# pwr_supply_controller.net
KiCad netlist of a schematic drawn in EAGLE
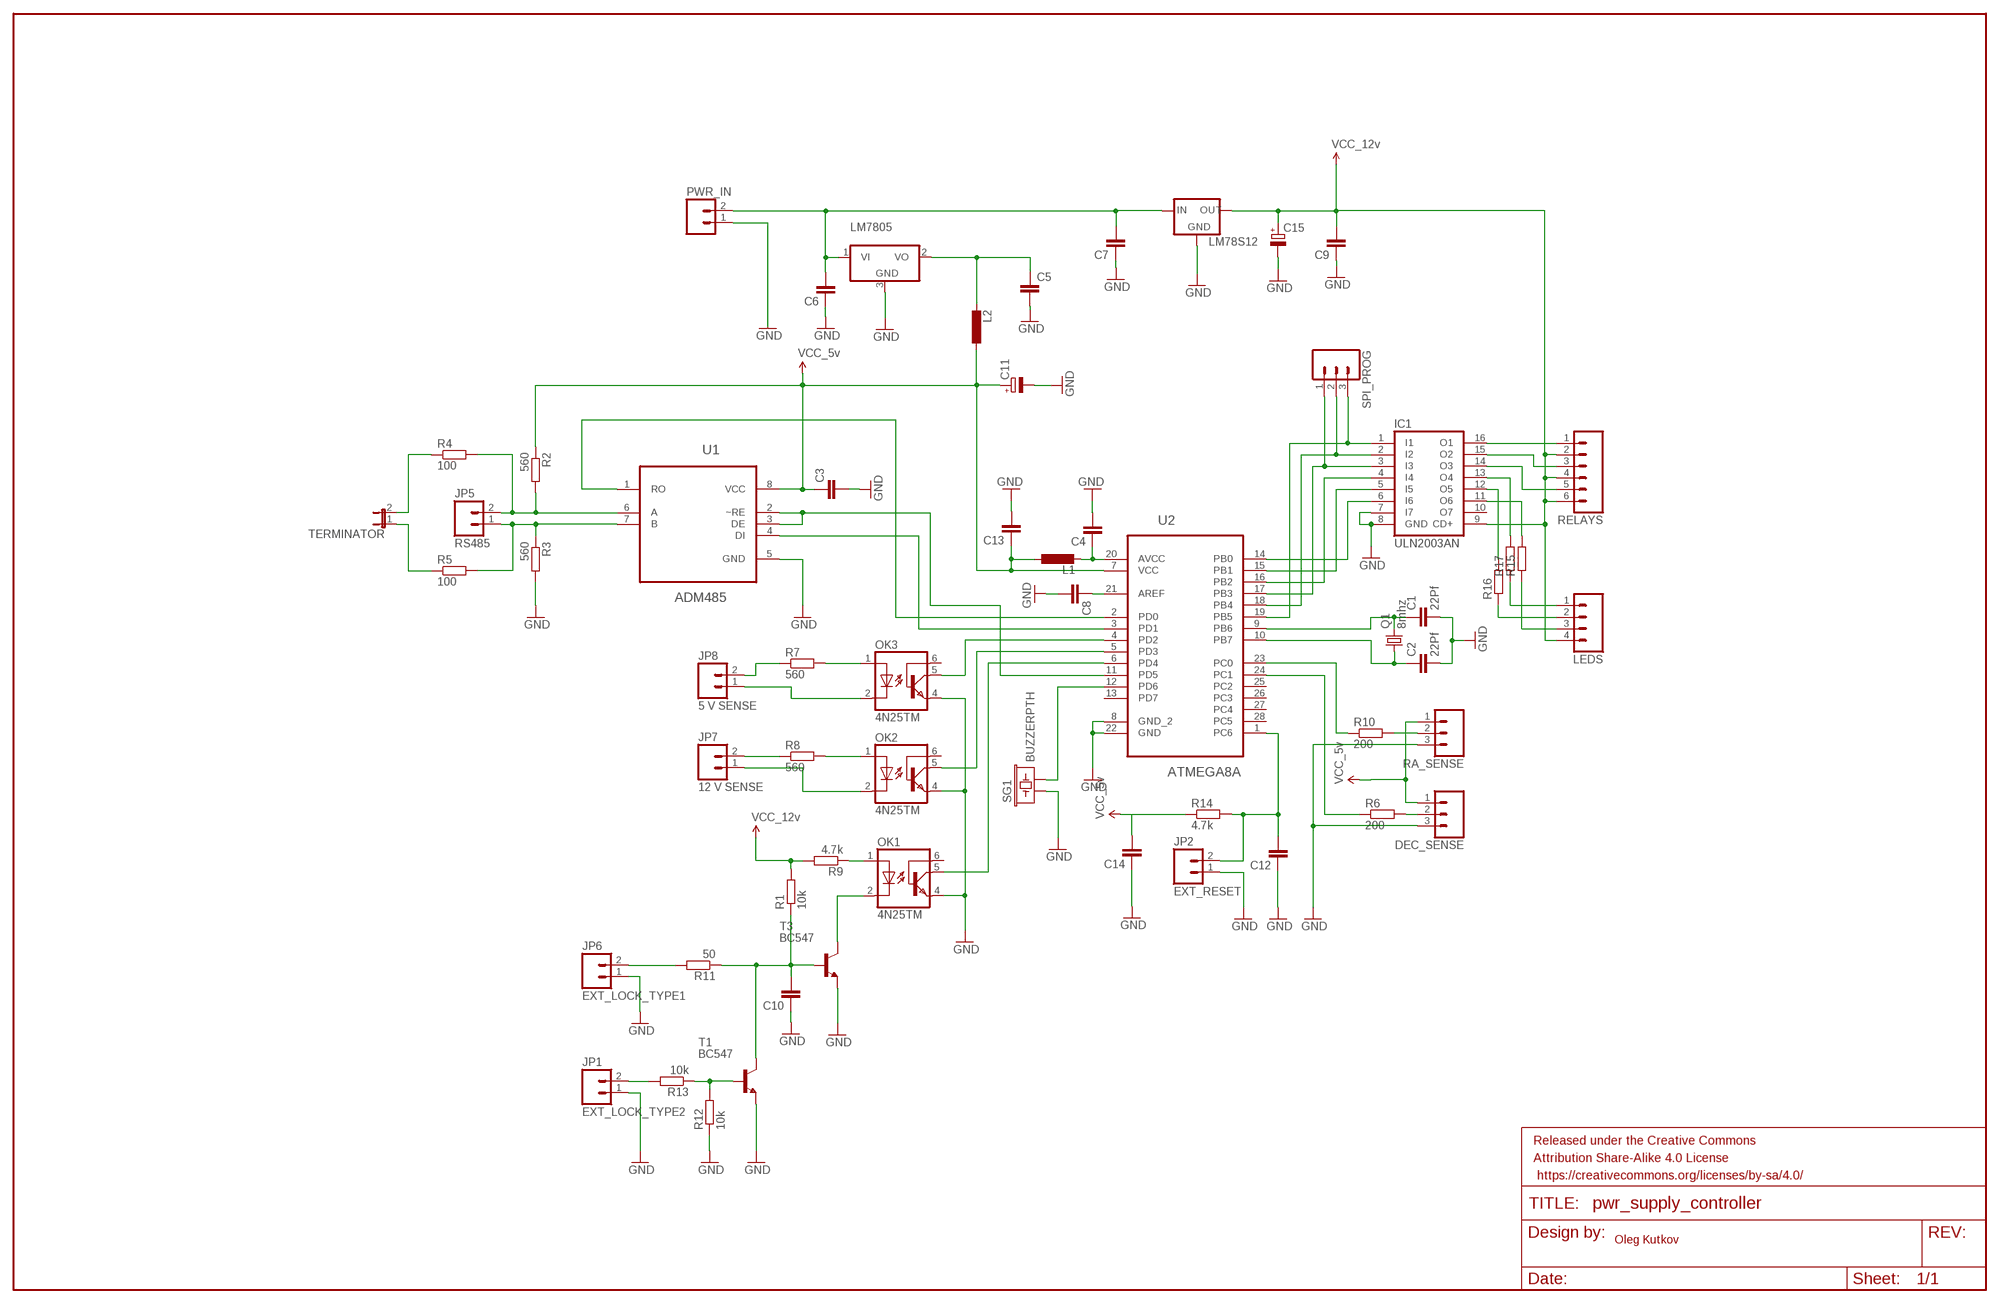
[diagram p0: schematic, sheet 1]

(export (version "E")
  (design (tool "Eeschema 10.0.6"))
  (components
    (comp (ref "C1")
      (value "22Pf")
      (footprint "eagle-import:C0603K")
      (libsource (lib "eagle-import") (part "C-EUC0603K"))
    )
    (comp (ref "C2")
      (value "22Pf")
      (footprint "eagle-import:C0603K")
      (libsource (lib "eagle-import") (part "C-EUC0603K"))
    )
    (comp (ref "C3")
      (value "C-EUC0603K")
      (footprint "eagle-import:C0603K")
      (libsource (lib "eagle-import") (part "C-EUC0603K"))
    )
    (comp (ref "C4")
      (value "C-EUC0603K")
      (footprint "eagle-import:C0603K")
      (libsource (lib "eagle-import") (part "C-EUC0603K"))
    )
    (comp (ref "C5")
      (value "C-EUC0603K")
      (footprint "eagle-import:C0603K")
      (libsource (lib "eagle-import") (part "C-EUC0603K"))
    )
    (comp (ref "C6")
      (value "C-EUC0805")
      (footprint "eagle-import:C0805")
      (libsource (lib "eagle-import") (part "C-EUC0805"))
    )
    (comp (ref "C7")
      (value "C-EUC0805")
      (footprint "eagle-import:C0805")
      (libsource (lib "eagle-import") (part "C-EUC0805"))
    )
    (comp (ref "C8")
      (value "C-EUC0603K")
      (footprint "eagle-import:C0603K")
      (libsource (lib "eagle-import") (part "C-EUC0603K"))
    )
    (comp (ref "C9")
      (value "C-EUC0805")
      (footprint "eagle-import:C0805")
      (libsource (lib "eagle-import") (part "C-EUC0805"))
    )
    (comp (ref "C10")
      (value "C-EUC0603K")
      (footprint "eagle-import:C0603K")
      (libsource (lib "eagle-import") (part "C-EUC0603K"))
    )
    (comp (ref "C11")
      (value "CPOL-EUE2-5")
      (footprint "eagle-import:E2-5")
      (libsource (lib "eagle-import") (part "CPOL-EUE2-5"))
    )
    (comp (ref "C12")
      (value "C-EUC0603K")
      (footprint "eagle-import:C0603K")
      (libsource (lib "eagle-import") (part "C-EUC0603K"))
    )
    (comp (ref "C13")
      (value "C-EUC0603K")
      (footprint "eagle-import:C0603K")
      (libsource (lib "eagle-import") (part "C-EUC0603K"))
    )
    (comp (ref "C14")
      (value "C-EUC0603K")
      (footprint "eagle-import:C0603K")
      (libsource (lib "eagle-import") (part "C-EUC0603K"))
    )
    (comp (ref "C15")
      (value "CPOL-EUE3.5-8")
      (footprint "eagle-import:E3,5-8")
      (libsource (lib "eagle-import") (part "CPOL-EUE3.5-8"))
    )
    (comp (ref "DEC_SENSE")
      (value "M03PTH")
      (footprint "eagle-import:1X03")
      (libsource (lib "eagle-import") (part "M03PTH"))
    )
    (comp (ref "FRAME1")
      (value "FRAME-LEDGER")
      (footprint "eagle-import:CREATIVE_COMMONS")
      (libsource (lib "eagle-import") (part "FRAME-LEDGER"))
    )
    (comp (ref "IC1")
      (value "ULN2003AN")
      (footprint "eagle-import:DIL16")
      (libsource (lib "eagle-import") (part "ULN2003AN"))
    )
    (comp (ref "JP1")
      (value "EXT_LOCK_TYPE2")
      (footprint "eagle-import:JST-2-PTH-VERT")
      (libsource (lib "eagle-import") (part "M02JST-PTH-VERT"))
    )
    (comp (ref "JP2")
      (value "EXT_RESET")
      (footprint "eagle-import:1X02")
      (libsource (lib "eagle-import") (part "M02PTH"))
    )
    (comp (ref "JP5")
      (value "RS485")
      (footprint "eagle-import:JST-2-PTH-VERT")
      (libsource (lib "eagle-import") (part "M02JST-PTH-VERT"))
    )
    (comp (ref "JP6")
      (value "EXT_LOCK_TYPE1")
      (footprint "eagle-import:JST-2-PTH-VERT")
      (libsource (lib "eagle-import") (part "M02JST-PTH-VERT"))
    )
    (comp (ref "JP7")
      (value "12 V SENSE")
      (footprint "eagle-import:JST-2-PTH-VERT")
      (libsource (lib "eagle-import") (part "M02JST-PTH-VERT"))
    )
    (comp (ref "JP8")
      (value "5 V SENSE")
      (footprint "eagle-import:JST-2-PTH-VERT")
      (libsource (lib "eagle-import") (part "M02JST-PTH-VERT"))
    )
    (comp (ref "L1")
      (value "L-EU0204/7")
      (footprint "eagle-import:0204_7")
      (libsource (lib "eagle-import") (part "L-EU0204/7"))
    )
    (comp (ref "L2")
      (value "L-EU0204/7")
      (footprint "eagle-import:0204_7")
      (libsource (lib "eagle-import") (part "L-EU0204/7"))
    )
    (comp (ref "LEDS")
      (value "M04PTH")
      (footprint "eagle-import:1X04")
      (libsource (lib "eagle-import") (part "M04PTH"))
    )
    (comp (ref "LM78S12")
      (value "V_REG_78XX-TO-220")
      (footprint "eagle-import:TO-220-ALT")
      (libsource (lib "eagle-import") (part "V_REG_78XX-TO-220"))
    )
    (comp (ref "LM7805")
      (value "7808DT")
      (footprint "eagle-import:TO252")
      (libsource (lib "eagle-import") (part "78DT08"))
    )
    (comp (ref "OK1")
      (value "4N25TM")
      (footprint "eagle-import:DIL6-04")
      (libsource (lib "eagle-import") (part "4N?MT25"))
    )
    (comp (ref "OK2")
      (value "4N25TM")
      (footprint "eagle-import:DIL6-04")
      (libsource (lib "eagle-import") (part "4N?MT25"))
    )
    (comp (ref "OK3")
      (value "4N25TM")
      (footprint "eagle-import:DIL6-04")
      (libsource (lib "eagle-import") (part "4N?MT25"))
    )
    (comp (ref "PWR_IN")
      (value "M02JST-PTH-VERT")
      (footprint "eagle-import:JST-2-PTH-VERT")
      (libsource (lib "eagle-import") (part "M02JST-PTH-VERT"))
    )
    (comp (ref "Q1")
      (value "8mhz")
      (footprint "eagle-import:HC49_S")
      (libsource (lib "eagle-import") (part "CRYSTALHC49S"))
    )
    (comp (ref "R1")
      (value "10k")
      (footprint "eagle-import:0204_7")
      (libsource (lib "eagle-import") (part "resistor_R-EU_0204/7"))
    )
    (comp (ref "R2")
      (value "560")
      (footprint "eagle-import:M0805")
      (libsource (lib "eagle-import") (part "resistor_R-EU_M0805"))
    )
    (comp (ref "R3")
      (value "560")
      (footprint "eagle-import:M0805")
      (libsource (lib "eagle-import") (part "resistor_R-EU_M0805"))
    )
    (comp (ref "R4")
      (value "100")
      (footprint "eagle-import:R0805")
      (libsource (lib "eagle-import") (part "resistor_R-EU_R0805"))
    )
    (comp (ref "R5")
      (value "100")
      (footprint "eagle-import:M0805")
      (libsource (lib "eagle-import") (part "resistor_R-EU_M0805"))
    )
    (comp (ref "R6")
      (value "200")
      (footprint "eagle-import:M0805")
      (libsource (lib "eagle-import") (part "resistor_R-EU_M0805"))
    )
    (comp (ref "R7")
      (value "560")
      (footprint "eagle-import:0204_7")
      (libsource (lib "eagle-import") (part "resistor_R-EU_0204/7"))
    )
    (comp (ref "R8")
      (value "560")
      (footprint "eagle-import:0204_7")
      (libsource (lib "eagle-import") (part "resistor_R-EU_0204/7"))
    )
    (comp (ref "R9")
      (value "4.7k")
      (footprint "eagle-import:0204_7")
      (libsource (lib "eagle-import") (part "resistor_R-EU_0204/7"))
    )
    (comp (ref "R10")
      (value "200")
      (footprint "eagle-import:M0805")
      (libsource (lib "eagle-import") (part "resistor_R-EU_M0805"))
    )
    (comp (ref "R11")
      (value "50")
      (footprint "eagle-import:0204_7")
      (libsource (lib "eagle-import") (part "resistor_R-EU_0204/7"))
    )
    (comp (ref "R12")
      (value "10k")
      (footprint "eagle-import:0204_7")
      (libsource (lib "eagle-import") (part "resistor_R-EU_0204/7"))
    )
    (comp (ref "R13")
      (value "10k")
      (footprint "eagle-import:0204_7")
      (libsource (lib "eagle-import") (part "resistor_R-EU_0204/7"))
    )
    (comp (ref "R14")
      (value "4.7k")
      (footprint "eagle-import:M0805")
      (libsource (lib "eagle-import") (part "resistor_R-EU_M0805"))
    )
    (comp (ref "R15")
      (value "R-EU_M0805")
      (footprint "eagle-import:M0805")
      (libsource (lib "eagle-import") (part "R-EU_M0805"))
    )
    (comp (ref "R16")
      (value "R-EU_M0805")
      (footprint "eagle-import:M0805")
      (libsource (lib "eagle-import") (part "R-EU_M0805"))
    )
    (comp (ref "R17")
      (value "R-EU_M0805")
      (footprint "eagle-import:M0805")
      (libsource (lib "eagle-import") (part "R-EU_M0805"))
    )
    (comp (ref "RA_SENSE")
      (value "M03PTH")
      (footprint "eagle-import:1X03")
      (libsource (lib "eagle-import") (part "M03PTH"))
    )
    (comp (ref "RELAYS")
      (value "M06POLAR")
      (footprint "eagle-import:MOLEX-1X6")
      (libsource (lib "eagle-import") (part "M06POLAR"))
    )
    (comp (ref "SG1")
      (value "BUZZERPTH")
      (footprint "eagle-import:BUZZER-12MM")
      (libsource (lib "eagle-import") (part "BUZZERPTH"))
    )
    (comp (ref "SPI_PROG")
      (value "M03PTH")
      (footprint "eagle-import:1X03")
      (libsource (lib "eagle-import") (part "M03PTH"))
    )
    (comp (ref "T1")
      (value "BC547")
      (footprint "eagle-import:TO92")
      (libsource (lib "eagle-import") (part "BC547"))
    )
    (comp (ref "T3")
      (value "BC547")
      (footprint "eagle-import:TO92")
      (libsource (lib "eagle-import") (part "BC547"))
    )
    (comp (ref "TERMINATOR")
      (value "JUMPER-2PTH_LOCK")
      (footprint "eagle-import:1X02_LOCK")
      (libsource (lib "eagle-import") (part "JUMPER-2PTH_LOCK"))
    )
    (comp (ref "U1")
      (value "ADM485")
      (footprint "eagle-import:SOIC127P600X175-8N")
      (fields (field (name "MPN") "MAX487ECSA+"))
      (libsource (lib "eagle-import") (part "MAX487ECSA+"))
    )
    (comp (ref "U2")
      (value "ATMEGA8A")
      (footprint "eagle-import:DIP254P762X457-28")
      (fields (field (name "MPN") "ATMEGA48A-PU"))
      (libsource (lib "eagle-import") (part "ATMEGA48A-PU"))
    )
  )
  (nets
    (net (code "1") (name "GND") (class "Default")
      (node (ref "C1") (pin "2") (pinfunction "2_2") (pintype "passive"))
      (node (ref "C10") (pin "1") (pinfunction "1_1") (pintype "passive"))
      (node (ref "C11") (pin "-") (pinfunction "-_-") (pintype "passive"))
      (node (ref "C12") (pin "1") (pinfunction "1_1") (pintype "passive"))
      (node (ref "C13") (pin "2") (pinfunction "2_2") (pintype "passive"))
      (node (ref "C14") (pin "1") (pinfunction "1_1") (pintype "passive"))
      (node (ref "C15") (pin "-") (pinfunction "-_-") (pintype "passive"))
      (node (ref "C2") (pin "2") (pinfunction "2_2") (pintype "passive"))
      (node (ref "C3") (pin "2") (pinfunction "2_2") (pintype "passive"))
      (node (ref "C4") (pin "2") (pinfunction "2_2") (pintype "passive"))
      (node (ref "C5") (pin "2") (pinfunction "2_2") (pintype "passive"))
      (node (ref "C6") (pin "1") (pinfunction "1_1") (pintype "passive"))
      (node (ref "C7") (pin "1") (pinfunction "1_1") (pintype "passive"))
      (node (ref "C8") (pin "2") (pinfunction "2_2") (pintype "passive"))
      (node (ref "C9") (pin "1") (pinfunction "1_1") (pintype "passive"))
      (node (ref "DEC_SENSE") (pin "3") (pinfunction "3_3") (pintype "passive"))
      (node (ref "IC1") (pin "7") (pinfunction "I7_7") (pintype "input"))
      (node (ref "IC1") (pin "8") (pinfunction "GND_8") (pintype "power_in"))
      (node (ref "JP1") (pin "1") (pinfunction "1_1") (pintype "passive"))
      (node (ref "JP2") (pin "1") (pinfunction "1_1") (pintype "passive"))
      (node (ref "JP6") (pin "1") (pinfunction "1_1") (pintype "passive"))
      (node (ref "LM7805") (pin "3") (pinfunction "GND_3") (pintype "passive"))
      (node (ref "LM78S12") (pin "GND") (pinfunction "GND_GND") (pintype "input"))
      (node (ref "OK1") (pin "4") (pinfunction "EMI_4") (pintype "passive"))
      (node (ref "OK2") (pin "4") (pinfunction "EMI_4") (pintype "passive"))
      (node (ref "OK3") (pin "4") (pinfunction "EMI_4") (pintype "passive"))
      (node (ref "PWR_IN") (pin "1") (pinfunction "1_1") (pintype "passive"))
      (node (ref "R12") (pin "1") (pinfunction "1_1") (pintype "passive"))
      (node (ref "R3") (pin "2") (pinfunction "2_2") (pintype "passive"))
      (node (ref "RA_SENSE") (pin "3") (pinfunction "3_3") (pintype "passive"))
      (node (ref "SG1") (pin "+") (pinfunction "1_+") (pintype "passive"))
      (node (ref "T1") (pin "1") (pinfunction "E_1") (pintype "passive"))
      (node (ref "T3") (pin "1") (pinfunction "E_1") (pintype "passive"))
      (node (ref "U1") (pin "5") (pinfunction "GND_5") (pintype "passive"))
      (node (ref "U2") (pin "22") (pinfunction "GND_22") (pintype "passive"))
      (node (ref "U2") (pin "8") (pinfunction "GND_2_8") (pintype "passive"))
    )
    (net (code "2") (name "Net-(DEC_SENSE-Pad2)") (class "Default")
      (node (ref "DEC_SENSE") (pin "2") (pinfunction "2_2") (pintype "passive"))
      (node (ref "R6") (pin "2") (pinfunction "2_2") (pintype "passive"))
    )
    (net (code "3") (name "Net-(IC1-I1)") (class "Default")
      (node (ref "IC1") (pin "1") (pinfunction "I1_1") (pintype "input"))
      (node (ref "SPI_PROG") (pin "3") (pinfunction "3_3") (pintype "passive"))
      (node (ref "U2") (pin "19") (pinfunction "PB5_19") (pintype "bidirectional"))
    )
    (net (code "4") (name "Net-(IC1-I2)") (class "Default")
      (node (ref "IC1") (pin "2") (pinfunction "I2_2") (pintype "input"))
      (node (ref "SPI_PROG") (pin "2") (pinfunction "2_2") (pintype "passive"))
      (node (ref "U2") (pin "18") (pinfunction "PB4_18") (pintype "bidirectional"))
    )
    (net (code "5") (name "Net-(IC1-I3)") (class "Default")
      (node (ref "IC1") (pin "3") (pinfunction "I3_3") (pintype "input"))
      (node (ref "SPI_PROG") (pin "1") (pinfunction "1_1") (pintype "passive"))
      (node (ref "U2") (pin "17") (pinfunction "PB3_17") (pintype "bidirectional"))
    )
    (net (code "6") (name "Net-(IC1-I4)") (class "Default")
      (node (ref "IC1") (pin "4") (pinfunction "I4_4") (pintype "input"))
      (node (ref "U2") (pin "16") (pinfunction "PB2_16") (pintype "bidirectional"))
    )
    (net (code "7") (name "Net-(IC1-I5)") (class "Default")
      (node (ref "IC1") (pin "5") (pinfunction "I5_5") (pintype "input"))
      (node (ref "U2") (pin "15") (pinfunction "PB1_15") (pintype "bidirectional"))
    )
    (net (code "8") (name "Net-(IC1-I6)") (class "Default")
      (node (ref "IC1") (pin "6") (pinfunction "I6_6") (pintype "input"))
      (node (ref "U2") (pin "14") (pinfunction "PB0_14") (pintype "bidirectional"))
    )
    (net (code "9") (name "Net-(IC1-O1)") (class "Default")
      (node (ref "IC1") (pin "16") (pinfunction "O1_16") (pintype "open_collector"))
      (node (ref "RELAYS") (pin "1") (pinfunction "1_1") (pintype "passive"))
    )
    (net (code "10") (name "Net-(IC1-O2)") (class "Default")
      (node (ref "IC1") (pin "15") (pinfunction "O2_15") (pintype "open_collector"))
      (node (ref "RELAYS") (pin "3") (pinfunction "3_3") (pintype "passive"))
    )
    (net (code "11") (name "Net-(IC1-O3)") (class "Default")
      (node (ref "IC1") (pin "14") (pinfunction "O3_14") (pintype "open_collector"))
      (node (ref "RELAYS") (pin "5") (pinfunction "5_5") (pintype "passive"))
    )
    (net (code "12") (name "Net-(IC1-O4)") (class "Default")
      (node (ref "IC1") (pin "13") (pinfunction "O4_13") (pintype "open_collector"))
      (node (ref "R17") (pin "2") (pinfunction "2_2") (pintype "passive"))
    )
    (net (code "13") (name "Net-(IC1-O5)") (class "Default")
      (node (ref "IC1") (pin "12") (pinfunction "O5_12") (pintype "open_collector"))
      (node (ref "R16") (pin "2") (pinfunction "2_2") (pintype "passive"))
    )
    (net (code "14") (name "Net-(IC1-O6)") (class "Default")
      (node (ref "IC1") (pin "11") (pinfunction "O6_11") (pintype "open_collector"))
      (node (ref "R15") (pin "2") (pinfunction "2_2") (pintype "passive"))
    )
    (net (code "15") (name "Net-(JP1-Pad2)") (class "Default")
      (node (ref "JP1") (pin "2") (pinfunction "2_2") (pintype "passive"))
      (node (ref "R13") (pin "2") (pinfunction "2_2") (pintype "passive"))
    )
    (net (code "16") (name "Net-(JP6-Pad2)") (class "Default")
      (node (ref "JP6") (pin "2") (pinfunction "2_2") (pintype "passive"))
      (node (ref "R11") (pin "2") (pinfunction "2_2") (pintype "passive"))
    )
    (net (code "17") (name "Net-(JP7-Pad2)") (class "Default")
      (node (ref "JP7") (pin "2") (pinfunction "2_2") (pintype "passive"))
      (node (ref "R8") (pin "1") (pinfunction "1_1") (pintype "passive"))
    )
    (net (code "18") (name "Net-(JP8-Pad2)") (class "Default")
      (node (ref "JP8") (pin "2") (pinfunction "2_2") (pintype "passive"))
      (node (ref "R7") (pin "1") (pinfunction "1_1") (pintype "passive"))
    )
    (net (code "19") (name "Net-(LEDS-Pad1)") (class "Default")
      (node (ref "LEDS") (pin "1") (pinfunction "1_1") (pintype "passive"))
      (node (ref "R17") (pin "1") (pinfunction "1_1") (pintype "passive"))
    )
    (net (code "20") (name "Net-(LEDS-Pad2)") (class "Default")
      (node (ref "LEDS") (pin "2") (pinfunction "2_2") (pintype "passive"))
      (node (ref "R16") (pin "1") (pinfunction "1_1") (pintype "passive"))
    )
    (net (code "21") (name "Net-(LEDS-Pad3)") (class "Default")
      (node (ref "LEDS") (pin "3") (pinfunction "3_3") (pintype "passive"))
      (node (ref "R15") (pin "1") (pinfunction "1_1") (pintype "passive"))
    )
    (net (code "22") (name "Net-(LM7805-VI)") (class "Default")
      (node (ref "C6") (pin "2") (pinfunction "2_2") (pintype "passive"))
      (node (ref "C7") (pin "2") (pinfunction "2_2") (pintype "passive"))
      (node (ref "LM7805") (pin "1") (pinfunction "VI_1") (pintype "input"))
      (node (ref "LM78S12") (pin "IN") (pinfunction "IN_IN") (pintype "input"))
      (node (ref "PWR_IN") (pin "2") (pinfunction "2_2") (pintype "passive"))
    )
    (net (code "23") (name "Net-(LM7805-VO)") (class "Default")
      (node (ref "C5") (pin "1") (pinfunction "1_1") (pintype "passive"))
      (node (ref "L2") (pin "2") (pinfunction "2_2") (pintype "passive"))
      (node (ref "LM7805") (pin "2") (pinfunction "VO_2") (pintype "passive"))
    )
    (net (code "24") (name "Net-(OK1-A)") (class "Default")
      (node (ref "OK1") (pin "1") (pinfunction "A_1") (pintype "passive"))
      (node (ref "R9") (pin "1") (pinfunction "1_1") (pintype "passive"))
    )
    (net (code "25") (name "Net-(OK1-C)") (class "Default")
      (node (ref "OK1") (pin "2") (pinfunction "C_2") (pintype "passive"))
      (node (ref "T3") (pin "3") (pinfunction "C_3") (pintype "passive"))
    )
    (net (code "26") (name "Net-(OK1-COL)") (class "Default")
      (node (ref "OK1") (pin "5") (pinfunction "COL_5") (pintype "passive"))
      (node (ref "U2") (pin "6") (pinfunction "PD4_6") (pintype "bidirectional"))
    )
    (net (code "27") (name "Net-(OK2-A)") (class "Default")
      (node (ref "OK2") (pin "1") (pinfunction "A_1") (pintype "passive"))
      (node (ref "R8") (pin "2") (pinfunction "2_2") (pintype "passive"))
    )
    (net (code "28") (name "Net-(OK2-C)") (class "Default")
      (node (ref "JP7") (pin "1") (pinfunction "1_1") (pintype "passive"))
      (node (ref "OK2") (pin "2") (pinfunction "C_2") (pintype "passive"))
    )
    (net (code "29") (name "Net-(OK2-COL)") (class "Default")
      (node (ref "OK2") (pin "5") (pinfunction "COL_5") (pintype "passive"))
      (node (ref "U2") (pin "5") (pinfunction "PD3_5") (pintype "bidirectional"))
    )
    (net (code "30") (name "Net-(OK3-A)") (class "Default")
      (node (ref "OK3") (pin "1") (pinfunction "A_1") (pintype "passive"))
      (node (ref "R7") (pin "2") (pinfunction "2_2") (pintype "passive"))
    )
    (net (code "31") (name "Net-(OK3-C)") (class "Default")
      (node (ref "JP8") (pin "1") (pinfunction "1_1") (pintype "passive"))
      (node (ref "OK3") (pin "2") (pinfunction "C_2") (pintype "passive"))
    )
    (net (code "32") (name "Net-(OK3-COL)") (class "Default")
      (node (ref "OK3") (pin "5") (pinfunction "COL_5") (pintype "passive"))
      (node (ref "U2") (pin "4") (pinfunction "PD2_4") (pintype "bidirectional"))
    )
    (net (code "33") (name "Net-(R4-Pad1)") (class "Default")
      (node (ref "R4") (pin "1") (pinfunction "1_1") (pintype "passive"))
      (node (ref "TERMINATOR") (pin "2") (pinfunction "2_2") (pintype "passive"))
    )
    (net (code "34") (name "Net-(R5-Pad1)") (class "Default")
      (node (ref "R5") (pin "1") (pinfunction "1_1") (pintype "passive"))
      (node (ref "TERMINATOR") (pin "1") (pinfunction "1_1") (pintype "passive"))
    )
    (net (code "35") (name "Net-(R10-Pad2)") (class "Default")
      (node (ref "R10") (pin "2") (pinfunction "2_2") (pintype "passive"))
      (node (ref "RA_SENSE") (pin "2") (pinfunction "2_2") (pintype "passive"))
    )
    (net (code "36") (name "Net-(SG1-2)") (class "Default")
      (node (ref "SG1") (pin "-") (pinfunction "2_-") (pintype "passive"))
      (node (ref "U2") (pin "12") (pinfunction "PD6_12") (pintype "bidirectional"))
    )
    (net (code "37") (name "Net-(T1-B)") (class "Default")
      (node (ref "R12") (pin "2") (pinfunction "2_2") (pintype "passive"))
      (node (ref "R13") (pin "1") (pinfunction "1_1") (pintype "passive"))
      (node (ref "T1") (pin "2") (pinfunction "B_2") (pintype "passive"))
    )
    (net (code "38") (name "Net-(T1-C)") (class "Default")
      (node (ref "C10") (pin "2") (pinfunction "2_2") (pintype "passive"))
      (node (ref "R1") (pin "1") (pinfunction "1_1") (pintype "passive"))
      (node (ref "R11") (pin "1") (pinfunction "1_1") (pintype "passive"))
      (node (ref "T1") (pin "3") (pinfunction "C_3") (pintype "passive"))
      (node (ref "T3") (pin "2") (pinfunction "B_2") (pintype "passive"))
    )
    (net (code "39") (name "Net-(U1-A)") (class "Default")
      (node (ref "JP5") (pin "2") (pinfunction "2_2") (pintype "passive"))
      (node (ref "R2") (pin "2") (pinfunction "2_2") (pintype "passive"))
      (node (ref "R4") (pin "2") (pinfunction "2_2") (pintype "passive"))
      (node (ref "U1") (pin "6") (pinfunction "A_6") (pintype "bidirectional"))
    )
    (net (code "40") (name "Net-(U1-B)") (class "Default")
      (node (ref "JP5") (pin "1") (pinfunction "1_1") (pintype "passive"))
      (node (ref "R3") (pin "1") (pinfunction "1_1") (pintype "passive"))
      (node (ref "R5") (pin "2") (pinfunction "2_2") (pintype "passive"))
      (node (ref "U1") (pin "7") (pinfunction "B_7") (pintype "bidirectional"))
    )
    (net (code "41") (name "Net-(U1-DE)") (class "Default")
      (node (ref "U1") (pin "2") (pinfunction "~{RE}_2") (pintype "input"))
      (node (ref "U1") (pin "3") (pinfunction "DE_3") (pintype "input"))
      (node (ref "U2") (pin "11") (pinfunction "PD5_11") (pintype "bidirectional"))
    )
    (net (code "42") (name "Net-(U1-DI)") (class "Default")
      (node (ref "U1") (pin "4") (pinfunction "DI_4") (pintype "input"))
      (node (ref "U2") (pin "3") (pinfunction "PD1_3") (pintype "bidirectional"))
    )
    (net (code "43") (name "Net-(U1-RO)") (class "Default")
      (node (ref "U1") (pin "1") (pinfunction "RO_1") (pintype "output"))
      (node (ref "U2") (pin "2") (pinfunction "PD0_2") (pintype "bidirectional"))
    )
    (net (code "44") (name "Net-(U2-AREF)") (class "Default")
      (node (ref "C8") (pin "1") (pinfunction "1_1") (pintype "passive"))
      (node (ref "U2") (pin "21") (pinfunction "AREF_21") (pintype "input"))
    )
    (net (code "45") (name "Net-(U2-AVCC)") (class "Default")
      (node (ref "C4") (pin "1") (pinfunction "1_1") (pintype "passive"))
      (node (ref "L1") (pin "2") (pinfunction "2_2") (pintype "passive"))
      (node (ref "U2") (pin "20") (pinfunction "AVCC_20") (pintype "power_in"))
    )
    (net (code "46") (name "Net-(U2-PB6)") (class "Default")
      (node (ref "C1") (pin "1") (pinfunction "1_1") (pintype "passive"))
      (node (ref "Q1") (pin "2") (pinfunction "2_2") (pintype "passive"))
      (node (ref "U2") (pin "9") (pinfunction "PB6_9") (pintype "bidirectional"))
    )
    (net (code "47") (name "Net-(U2-PB7)") (class "Default")
      (node (ref "C2") (pin "1") (pinfunction "1_1") (pintype "passive"))
      (node (ref "Q1") (pin "1") (pinfunction "1_1") (pintype "passive"))
      (node (ref "U2") (pin "10") (pinfunction "PB7_10") (pintype "bidirectional"))
    )
    (net (code "48") (name "Net-(U2-PC0)") (class "Default")
      (node (ref "R10") (pin "1") (pinfunction "1_1") (pintype "passive"))
      (node (ref "U2") (pin "23") (pinfunction "PC0_23") (pintype "bidirectional"))
    )
    (net (code "49") (name "Net-(U2-PC1)") (class "Default")
      (node (ref "R6") (pin "1") (pinfunction "1_1") (pintype "passive"))
      (node (ref "U2") (pin "24") (pinfunction "PC1_24") (pintype "bidirectional"))
    )
    (net (code "50") (name "Net-(U2-PC6)") (class "Default")
      (node (ref "C12") (pin "2") (pinfunction "2_2") (pintype "passive"))
      (node (ref "JP2") (pin "2") (pinfunction "2_2") (pintype "passive"))
      (node (ref "R14") (pin "2") (pinfunction "2_2") (pintype "passive"))
      (node (ref "U2") (pin "1") (pinfunction "PC6_1") (pintype "bidirectional"))
    )
    (net (code "51") (name "VCC_5v") (class "Default")
      (node (ref "C11") (pin "+") (pinfunction "+_+") (pintype "passive"))
      (node (ref "C13") (pin "1") (pinfunction "1_1") (pintype "passive"))
      (node (ref "C14") (pin "2") (pinfunction "2_2") (pintype "passive"))
      (node (ref "C3") (pin "1") (pinfunction "1_1") (pintype "passive"))
      (node (ref "DEC_SENSE") (pin "1") (pinfunction "1_1") (pintype "passive"))
      (node (ref "L1") (pin "1") (pinfunction "1_1") (pintype "passive"))
      (node (ref "L2") (pin "1") (pinfunction "1_1") (pintype "passive"))
      (node (ref "R14") (pin "1") (pinfunction "1_1") (pintype "passive"))
      (node (ref "R2") (pin "1") (pinfunction "1_1") (pintype "passive"))
      (node (ref "RA_SENSE") (pin "1") (pinfunction "1_1") (pintype "passive"))
      (node (ref "U1") (pin "8") (pinfunction "VCC_8") (pintype "power_in"))
      (node (ref "U2") (pin "7") (pinfunction "VCC_7") (pintype "power_in"))
    )
    (net (code "52") (name "VCC_12v") (class "Default")
      (node (ref "C15") (pin "+") (pinfunction "+_+") (pintype "passive"))
      (node (ref "C9") (pin "2") (pinfunction "2_2") (pintype "passive"))
      (node (ref "IC1") (pin "9") (pinfunction "CD+_9") (pintype "passive"))
      (node (ref "LEDS") (pin "4") (pinfunction "4_4") (pintype "passive"))
      (node (ref "LM78S12") (pin "OUT") (pinfunction "OUT_OUT") (pintype "output"))
      (node (ref "R1") (pin "2") (pinfunction "2_2") (pintype "passive"))
      (node (ref "R9") (pin "2") (pinfunction "2_2") (pintype "passive"))
      (node (ref "RELAYS") (pin "2") (pinfunction "2_2") (pintype "passive"))
      (node (ref "RELAYS") (pin "4") (pinfunction "4_4") (pintype "passive"))
      (node (ref "RELAYS") (pin "6") (pinfunction "6_6") (pintype "passive"))
    )
    (net (code "53") (name "unconnected-(IC1-O7-Pad10)") (class "Default")
      (node (ref "IC1") (pin "10") (pinfunction "O7_10") (pintype "open_collector"))
    )
    (net (code "54") (name "unconnected-(OK1-BAS-Pad6)") (class "Default")
      (node (ref "OK1") (pin "6") (pinfunction "BAS_6") (pintype "passive"))
    )
    (net (code "55") (name "unconnected-(OK2-BAS-Pad6)") (class "Default")
      (node (ref "OK2") (pin "6") (pinfunction "BAS_6") (pintype "passive"))
    )
    (net (code "56") (name "unconnected-(OK3-BAS-Pad6)") (class "Default")
      (node (ref "OK3") (pin "6") (pinfunction "BAS_6") (pintype "passive"))
    )
    (net (code "57") (name "unconnected-(U2-PC2-Pad25)") (class "Default")
      (node (ref "U2") (pin "25") (pinfunction "PC2_25") (pintype "bidirectional"))
    )
    (net (code "58") (name "unconnected-(U2-PC3-Pad26)") (class "Default")
      (node (ref "U2") (pin "26") (pinfunction "PC3_26") (pintype "bidirectional"))
    )
    (net (code "59") (name "unconnected-(U2-PC4-Pad27)") (class "Default")
      (node (ref "U2") (pin "27") (pinfunction "PC4_27") (pintype "bidirectional"))
    )
    (net (code "60") (name "unconnected-(U2-PC5-Pad28)") (class "Default")
      (node (ref "U2") (pin "28") (pinfunction "PC5_28") (pintype "bidirectional"))
    )
    (net (code "61") (name "unconnected-(U2-PD7-Pad13)") (class "Default")
      (node (ref "U2") (pin "13") (pinfunction "PD7_13") (pintype "bidirectional"))
    )
  )
)
